# old_motorline.net
KiCad netlist of a schematic drawn in EAGLE
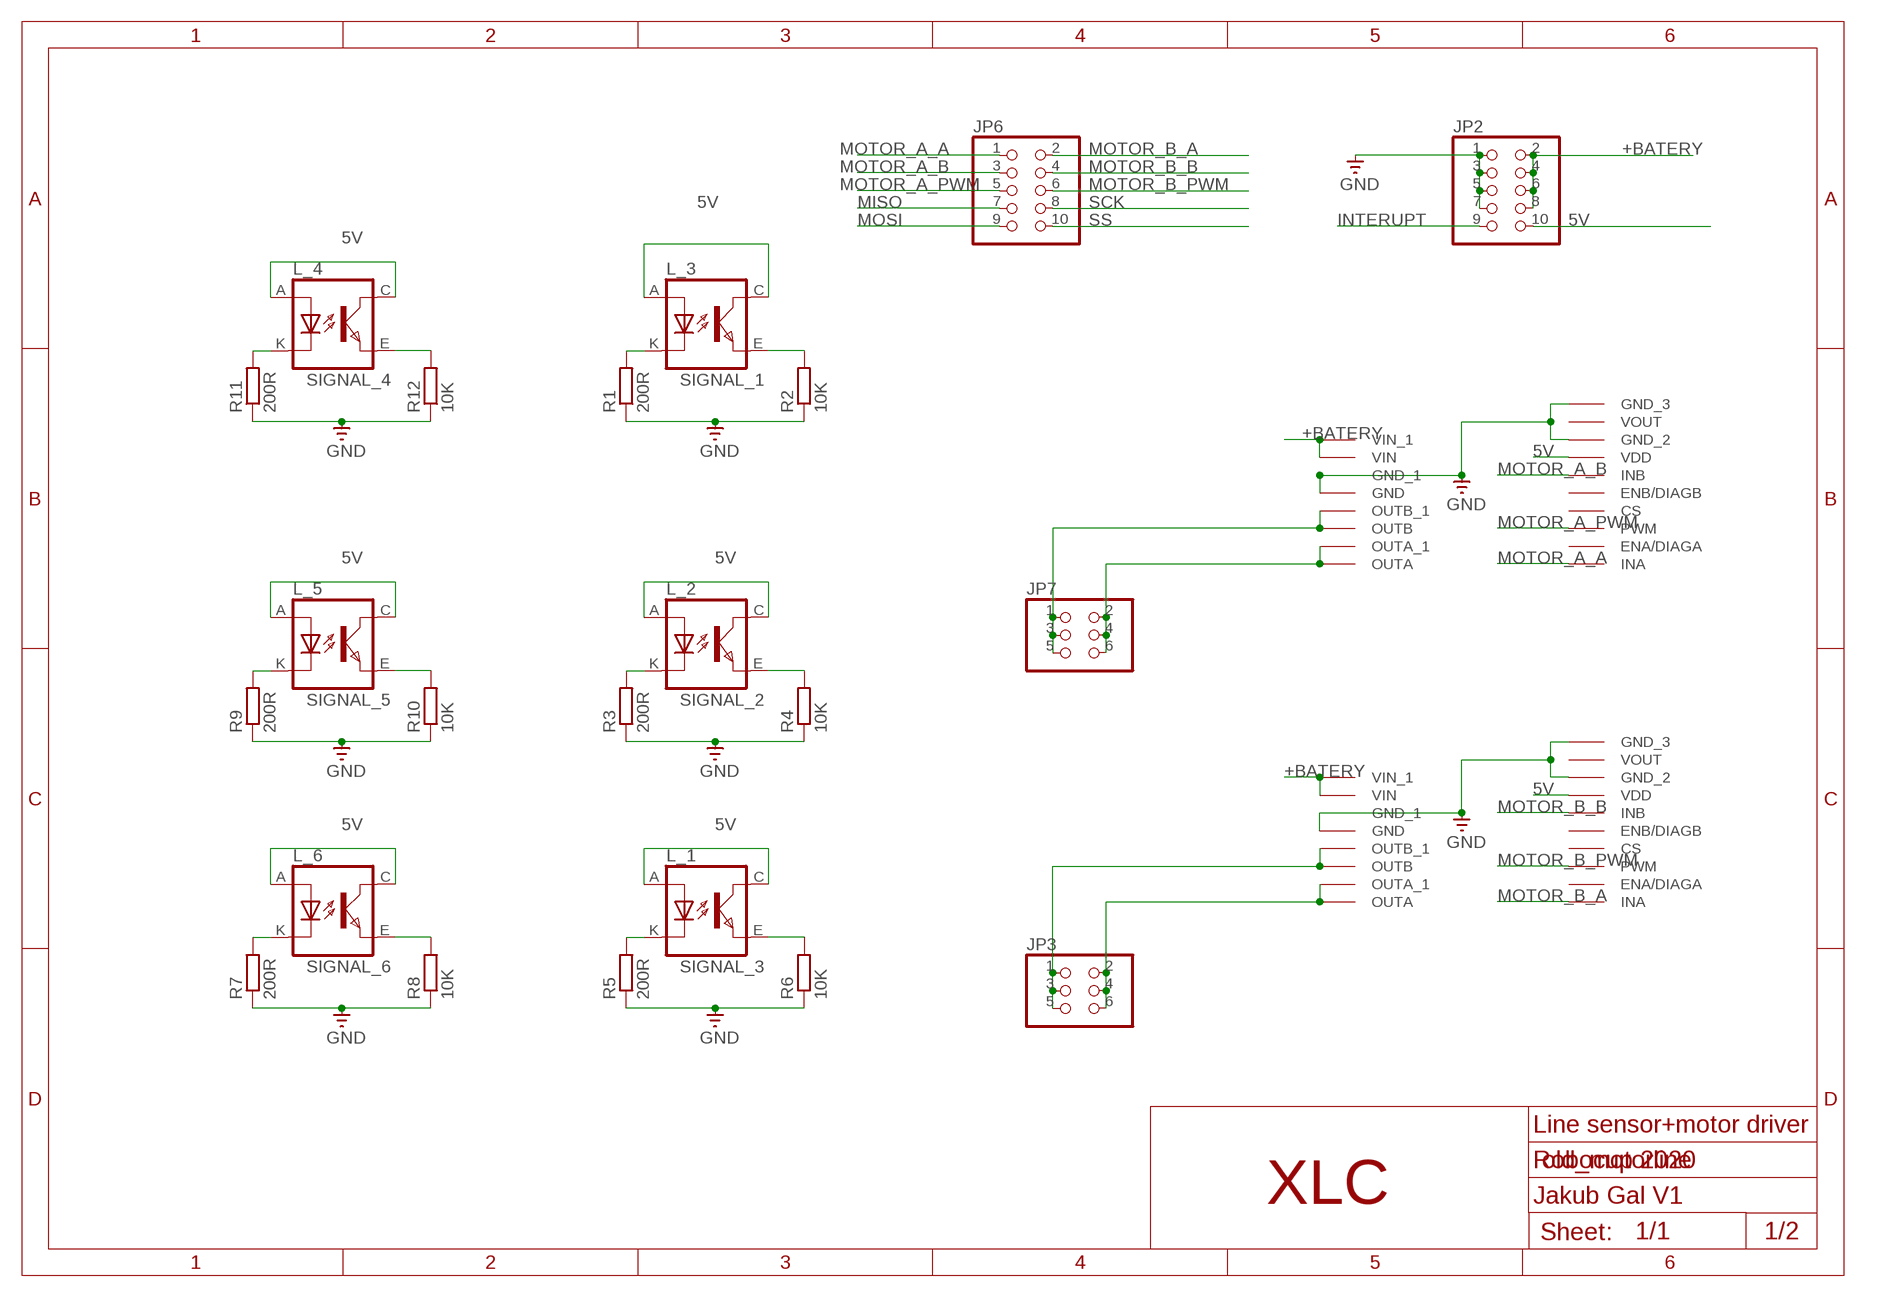
[diagram p0: schematic, sheet 1, part 1 of 2]
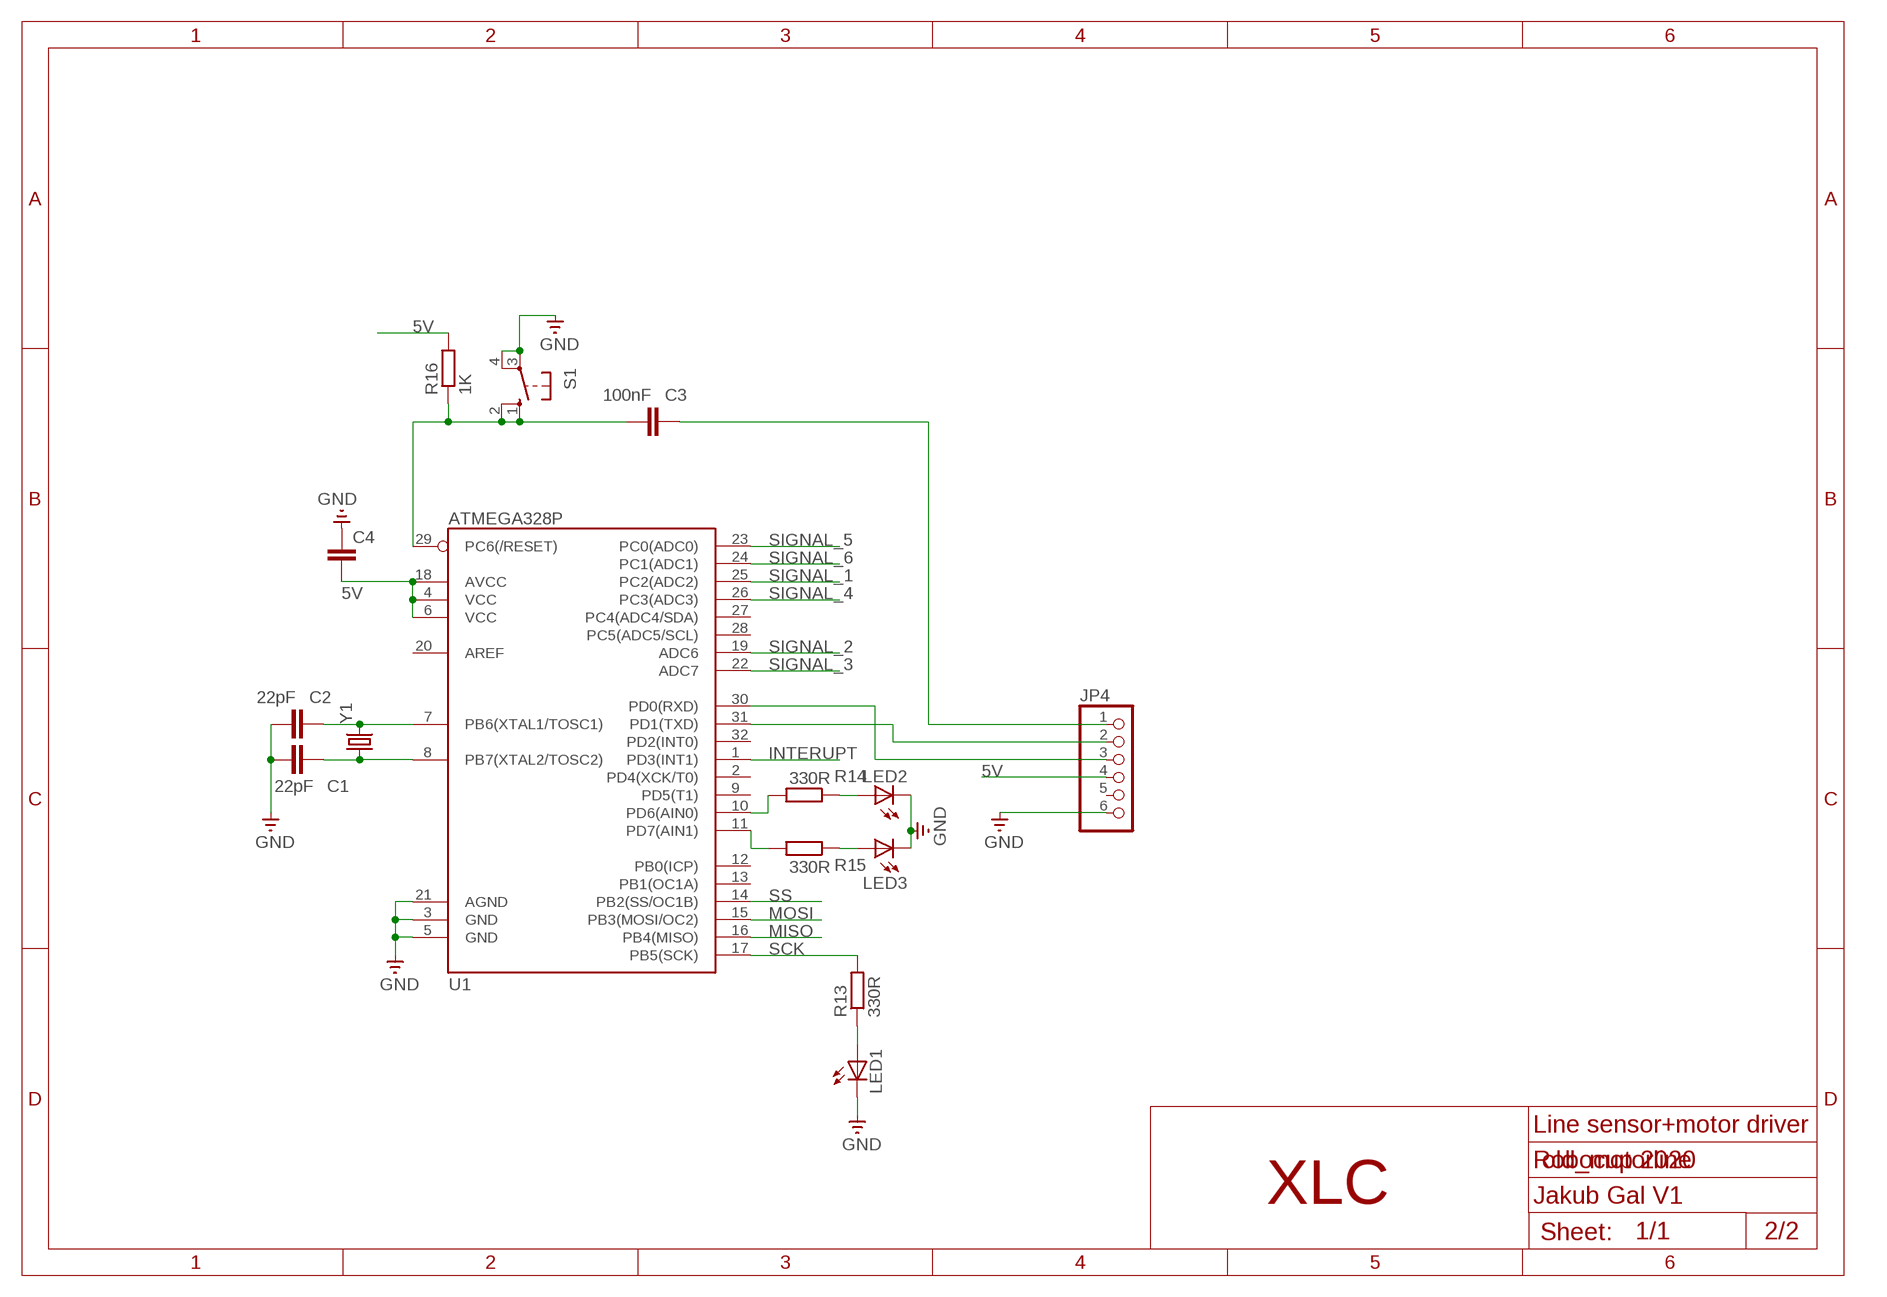
[diagram p1: schematic, sheet 1, part 2 of 2]

(export (version "E")
  (design (tool "Eeschema 10.0.6"))
  (components
    (comp (ref "C1")
      (value "22pF")
      (footprint "eagle-import:C0603")
      (libsource (lib "eagle-import") (part "rcl@1_C-EUC0603"))
    )
    (comp (ref "C2")
      (value "22pF")
      (footprint "eagle-import:C0603")
      (libsource (lib "eagle-import") (part "rcl@1_C-EUC0603"))
    )
    (comp (ref "C3")
      (value "100nF")
      (footprint "eagle-import:C0603")
      (libsource (lib "eagle-import") (part "rcl@1_C-EUC0603"))
    )
    (comp (ref "C4")
      (value "C-EUC0603")
      (footprint "eagle-import:C0603")
      (libsource (lib "eagle-import") (part "C-EUC0603"))
    )
    (comp (ref "JP2")
      (value "PINHD-2X5IDC")
      (footprint "eagle-import:2X05_IDC")
      (libsource (lib "eagle-import") (part "PINHD-2X5IDC"))
    )
    (comp (ref "JP3")
      (value "PINHD-2X3IDC")
      (footprint "eagle-import:2X03_IDC")
      (libsource (lib "eagle-import") (part "PINHD-2X3IDC"))
    )
    (comp (ref "JP4")
      (value "PINHD-1X6_2.54-90°")
      (footprint "eagle-import:1X06_90")
      (libsource (lib "eagle-import") (part "PINHD-1X6_2.54-90°"))
    )
    (comp (ref "JP6")
      (value "PINHD-2X5IDC")
      (footprint "eagle-import:2X05_IDC")
      (libsource (lib "eagle-import") (part "PINHD-2X5IDC"))
    )
    (comp (ref "JP7")
      (value "PINHD-2X3IDC")
      (footprint "eagle-import:2X03_IDC")
      (libsource (lib "eagle-import") (part "PINHD-2X3IDC"))
    )
    (comp (ref "LED1")
      (value "LEDCHIPLED_0603")
      (footprint "eagle-import:CHIPLED_0603")
      (libsource (lib "eagle-import") (part "LEDCHIPLED_0603"))
    )
    (comp (ref "LED2")
      (value "LEDCHIPLED_0603")
      (footprint "eagle-import:CHIPLED_0603")
      (libsource (lib "eagle-import") (part "LEDCHIPLED_0603"))
    )
    (comp (ref "LED3")
      (value "LEDCHIPLED_0603")
      (footprint "eagle-import:CHIPLED_0603")
      (libsource (lib "eagle-import") (part "LEDCHIPLED_0603"))
    )
    (comp (ref "L_1")
      (value "TCRT5000")
      (footprint "eagle-import:TCRT5000")
      (libsource (lib "eagle-import") (part "TCRT5000"))
    )
    (comp (ref "L_2")
      (value "TCRT5000")
      (footprint "eagle-import:TCRT5000")
      (libsource (lib "eagle-import") (part "TCRT5000"))
    )
    (comp (ref "L_3")
      (value "TCRT5000")
      (footprint "eagle-import:TCRT5000")
      (libsource (lib "eagle-import") (part "TCRT5000"))
    )
    (comp (ref "L_4")
      (value "TCRT5000")
      (footprint "eagle-import:TCRT5000")
      (fields (field (name "SPICEPREFIX") "O"))
      (libsource (lib "eagle-import") (part "TCRT5000"))
    )
    (comp (ref "L_5")
      (value "TCRT5000")
      (footprint "eagle-import:TCRT5000")
      (libsource (lib "eagle-import") (part "TCRT5000"))
    )
    (comp (ref "L_6")
      (value "TCRT5000")
      (footprint "eagle-import:TCRT5000")
      (fields (field (name "SPICEPREFIX") "O"))
      (libsource (lib "eagle-import") (part "TCRT5000"))
    )
    (comp (ref "R1")
      (value "200R")
      (footprint "eagle-import:R0603")
      (libsource (lib "eagle-import") (part "R-EU_R0603"))
    )
    (comp (ref "R2")
      (value "10K")
      (footprint "eagle-import:R0603")
      (libsource (lib "eagle-import") (part "R-EU_R0603"))
    )
    (comp (ref "R3")
      (value "200R")
      (footprint "eagle-import:R0603")
      (libsource (lib "eagle-import") (part "R-EU_R0603"))
    )
    (comp (ref "R4")
      (value "10K")
      (footprint "eagle-import:R0603")
      (libsource (lib "eagle-import") (part "R-EU_R0603"))
    )
    (comp (ref "R5")
      (value "200R")
      (footprint "eagle-import:R0603")
      (libsource (lib "eagle-import") (part "R-EU_R0603"))
    )
    (comp (ref "R6")
      (value "10K")
      (footprint "eagle-import:R0603")
      (libsource (lib "eagle-import") (part "R-EU_R0603"))
    )
    (comp (ref "R7")
      (value "200R")
      (footprint "eagle-import:R0603")
      (libsource (lib "eagle-import") (part "R-EU_R0603"))
    )
    (comp (ref "R8")
      (value "10K")
      (footprint "eagle-import:R0603")
      (libsource (lib "eagle-import") (part "R-EU_R0603"))
    )
    (comp (ref "R9")
      (value "200R")
      (footprint "eagle-import:R0603")
      (libsource (lib "eagle-import") (part "R-EU_R0603"))
    )
    (comp (ref "R10")
      (value "10K")
      (footprint "eagle-import:R0603")
      (libsource (lib "eagle-import") (part "R-EU_R0603"))
    )
    (comp (ref "R11")
      (value "200R")
      (footprint "eagle-import:R0603")
      (libsource (lib "eagle-import") (part "R-EU_R0603"))
    )
    (comp (ref "R12")
      (value "10K")
      (footprint "eagle-import:R0603")
      (libsource (lib "eagle-import") (part "R-EU_R0603"))
    )
    (comp (ref "R13")
      (value "330R")
      (footprint "eagle-import:R0603")
      (libsource (lib "eagle-import") (part "R-EU_R0603"))
    )
    (comp (ref "R14")
      (value "330R")
      (footprint "eagle-import:R0603")
      (libsource (lib "eagle-import") (part "R-EU_R0603"))
    )
    (comp (ref "R15")
      (value "330R")
      (footprint "eagle-import:R0603")
      (libsource (lib "eagle-import") (part "R-EU_R0603"))
    )
    (comp (ref "R16")
      (value "1K")
      (footprint "eagle-import:R0603")
      (libsource (lib "eagle-import") (part "R-EU_R0603"))
    )
    (comp (ref "S1")
      (value "10-XX")
      (footprint "eagle-import:B3F-10XX")
      (fields (field (name "MPN") "B3F-1000"))
      (libsource (lib "eagle-import") (part "10-XX"))
    )
    (comp (ref "U$1")
      (value "MOTOR_DRIVER")
      (footprint "eagle-import:MOTOR_DRIVER")
      (libsource (lib "eagle-import") (part "MOTOR_DRIVER"))
    )
    (comp (ref "U$2")
      (value "MOTOR_DRIVER")
      (footprint "eagle-import:MOTOR_DRIVER")
      (libsource (lib "eagle-import") (part "MOTOR_DRIVER"))
    )
    (comp (ref "U1")
      (value "ATMEGA328P")
      (footprint "eagle-import:TQFP32-08")
      (libsource (lib "eagle-import") (part "ATMEGA328_SMT"))
    )
    (comp (ref "Y1")
      (value "CRYSTALHC49US")
      (footprint "eagle-import:HC49US")
      (libsource (lib "eagle-import") (part "CRYSTALHC49US"))
    )
  )
  (nets
    (net (code "1") (name "/+BATERY") (class "Default")
      (node (ref "JP2") (pin "2") (pinfunction "2_2") (pintype "passive"))
      (node (ref "JP2") (pin "4") (pinfunction "4_4") (pintype "passive"))
      (node (ref "JP2") (pin "6") (pinfunction "6_6") (pintype "passive"))
      (node (ref "JP2") (pin "8") (pinfunction "8_8") (pintype "passive"))
      (node (ref "U$1") (pin "VIN") (pinfunction "VIN_VIN") (pintype "bidirectional"))
      (node (ref "U$1") (pin "VIN_1") (pinfunction "VIN_1_VIN_1") (pintype "bidirectional"))
      (node (ref "U$2") (pin "VIN") (pinfunction "VIN_VIN") (pintype "bidirectional"))
      (node (ref "U$2") (pin "VIN_1") (pinfunction "VIN_1_VIN_1") (pintype "bidirectional"))
    )
    (net (code "2") (name "/5V") (class "Default")
      (node (ref "C4") (pin "2") (pinfunction "2_2") (pintype "passive"))
      (node (ref "JP2") (pin "10") (pinfunction "10_10") (pintype "passive"))
      (node (ref "JP4") (pin "4") (pinfunction "4_4") (pintype "passive"))
      (node (ref "L_1") (pin "A") (pinfunction "ANODE_A") (pintype "passive"))
      (node (ref "L_1") (pin "C") (pinfunction "COLLECTOR_C") (pintype "passive"))
      (node (ref "L_2") (pin "A") (pinfunction "ANODE_A") (pintype "passive"))
      (node (ref "L_2") (pin "C") (pinfunction "COLLECTOR_C") (pintype "passive"))
      (node (ref "L_3") (pin "A") (pinfunction "ANODE_A") (pintype "passive"))
      (node (ref "L_3") (pin "C") (pinfunction "COLLECTOR_C") (pintype "passive"))
      (node (ref "L_4") (pin "A") (pinfunction "ANODE_A") (pintype "passive"))
      (node (ref "L_4") (pin "C") (pinfunction "COLLECTOR_C") (pintype "passive"))
      (node (ref "L_5") (pin "A") (pinfunction "ANODE_A") (pintype "passive"))
      (node (ref "L_5") (pin "C") (pinfunction "COLLECTOR_C") (pintype "passive"))
      (node (ref "L_6") (pin "A") (pinfunction "ANODE_A") (pintype "passive"))
      (node (ref "L_6") (pin "C") (pinfunction "COLLECTOR_C") (pintype "passive"))
      (node (ref "R16") (pin "2") (pinfunction "2_2") (pintype "passive"))
      (node (ref "U$1") (pin "VDD") (pinfunction "VDD_VDD") (pintype "bidirectional"))
      (node (ref "U$2") (pin "VDD") (pinfunction "VDD_VDD") (pintype "bidirectional"))
      (node (ref "U1") (pin "18") (pinfunction "AVCC_18") (pintype "bidirectional"))
      (node (ref "U1") (pin "4") (pinfunction "VCC_4") (pintype "bidirectional"))
      (node (ref "U1") (pin "6") (pinfunction "VCC_6") (pintype "bidirectional"))
    )
    (net (code "3") (name "/INTERUPT") (class "Default")
      (node (ref "JP2") (pin "9") (pinfunction "9_9") (pintype "passive"))
      (node (ref "U1") (pin "1") (pinfunction "PD3(INT1)_1") (pintype "bidirectional"))
    )
    (net (code "4") (name "/MISO") (class "Default")
      (node (ref "JP6") (pin "7") (pinfunction "7_7") (pintype "passive"))
      (node (ref "U1") (pin "16") (pinfunction "PB4(MISO)_16") (pintype "bidirectional"))
    )
    (net (code "5") (name "/MOSI") (class "Default")
      (node (ref "JP6") (pin "9") (pinfunction "9_9") (pintype "passive"))
      (node (ref "U1") (pin "15") (pinfunction "PB3(MOSI/OC2)_15") (pintype "bidirectional"))
    )
    (net (code "6") (name "/MOTOR_A_A") (class "Default")
      (node (ref "JP6") (pin "1") (pinfunction "1_1") (pintype "passive"))
      (node (ref "U$1") (pin "INA") (pinfunction "INA_INA") (pintype "bidirectional"))
    )
    (net (code "7") (name "/MOTOR_A_B") (class "Default")
      (node (ref "JP6") (pin "3") (pinfunction "3_3") (pintype "passive"))
      (node (ref "U$1") (pin "INB") (pinfunction "INB_INB") (pintype "bidirectional"))
    )
    (net (code "8") (name "/MOTOR_A_PWM") (class "Default")
      (node (ref "JP6") (pin "5") (pinfunction "5_5") (pintype "passive"))
      (node (ref "U$1") (pin "PWM") (pinfunction "PWM_PWM") (pintype "bidirectional"))
    )
    (net (code "9") (name "/MOTOR_B_A") (class "Default")
      (node (ref "JP6") (pin "2") (pinfunction "2_2") (pintype "passive"))
      (node (ref "U$2") (pin "INA") (pinfunction "INA_INA") (pintype "bidirectional"))
    )
    (net (code "10") (name "/MOTOR_B_B") (class "Default")
      (node (ref "JP6") (pin "4") (pinfunction "4_4") (pintype "passive"))
      (node (ref "U$2") (pin "INB") (pinfunction "INB_INB") (pintype "bidirectional"))
    )
    (net (code "11") (name "/MOTOR_B_PWM") (class "Default")
      (node (ref "JP6") (pin "6") (pinfunction "6_6") (pintype "passive"))
      (node (ref "U$2") (pin "PWM") (pinfunction "PWM_PWM") (pintype "bidirectional"))
    )
    (net (code "12") (name "/SCK") (class "Default")
      (node (ref "JP6") (pin "8") (pinfunction "8_8") (pintype "passive"))
      (node (ref "R13") (pin "2") (pinfunction "2_2") (pintype "passive"))
      (node (ref "U1") (pin "17") (pinfunction "PB5(SCK)_17") (pintype "bidirectional"))
    )
    (net (code "13") (name "/SIGNAL_1") (class "Default")
      (node (ref "L_3") (pin "E") (pinfunction "EMITTER_E") (pintype "passive"))
      (node (ref "R2") (pin "2") (pinfunction "2_2") (pintype "passive"))
      (node (ref "U1") (pin "25") (pinfunction "PC2(ADC2)_25") (pintype "bidirectional"))
    )
    (net (code "14") (name "/SIGNAL_2") (class "Default")
      (node (ref "L_2") (pin "E") (pinfunction "EMITTER_E") (pintype "passive"))
      (node (ref "R4") (pin "2") (pinfunction "2_2") (pintype "passive"))
      (node (ref "U1") (pin "19") (pinfunction "ADC6_19") (pintype "bidirectional"))
    )
    (net (code "15") (name "/SIGNAL_3") (class "Default")
      (node (ref "L_1") (pin "E") (pinfunction "EMITTER_E") (pintype "passive"))
      (node (ref "R6") (pin "2") (pinfunction "2_2") (pintype "passive"))
      (node (ref "U1") (pin "22") (pinfunction "ADC7_22") (pintype "bidirectional"))
    )
    (net (code "16") (name "/SIGNAL_4") (class "Default")
      (node (ref "L_4") (pin "E") (pinfunction "EMITTER_E") (pintype "passive"))
      (node (ref "R12") (pin "2") (pinfunction "2_2") (pintype "passive"))
      (node (ref "U1") (pin "26") (pinfunction "PC3(ADC3)_26") (pintype "bidirectional"))
    )
    (net (code "17") (name "/SIGNAL_5") (class "Default")
      (node (ref "L_5") (pin "E") (pinfunction "EMITTER_E") (pintype "passive"))
      (node (ref "R10") (pin "2") (pinfunction "2_2") (pintype "passive"))
      (node (ref "U1") (pin "23") (pinfunction "PC0(ADC0)_23") (pintype "bidirectional"))
    )
    (net (code "18") (name "/SIGNAL_6") (class "Default")
      (node (ref "L_6") (pin "E") (pinfunction "EMITTER_E") (pintype "passive"))
      (node (ref "R8") (pin "2") (pinfunction "2_2") (pintype "passive"))
      (node (ref "U1") (pin "24") (pinfunction "PC1(ADC1)_24") (pintype "bidirectional"))
    )
    (net (code "19") (name "/SS") (class "Default")
      (node (ref "JP6") (pin "10") (pinfunction "10_10") (pintype "passive"))
      (node (ref "U1") (pin "14") (pinfunction "PB2(SS/OC1B)_14") (pintype "bidirectional"))
    )
    (net (code "20") (name "GND") (class "Default")
      (node (ref "C1") (pin "1") (pinfunction "1_1") (pintype "passive"))
      (node (ref "C2") (pin "1") (pinfunction "1_1") (pintype "passive"))
      (node (ref "C4") (pin "1") (pinfunction "1_1") (pintype "passive"))
      (node (ref "JP2") (pin "1") (pinfunction "1_1") (pintype "passive"))
      (node (ref "JP2") (pin "3") (pinfunction "3_3") (pintype "passive"))
      (node (ref "JP2") (pin "5") (pinfunction "5_5") (pintype "passive"))
      (node (ref "JP2") (pin "7") (pinfunction "7_7") (pintype "passive"))
      (node (ref "JP4") (pin "6") (pinfunction "6_6") (pintype "passive"))
      (node (ref "LED1") (pin "C") (pinfunction "C_C") (pintype "passive"))
      (node (ref "LED2") (pin "C") (pinfunction "C_C") (pintype "passive"))
      (node (ref "LED3") (pin "C") (pinfunction "C_C") (pintype "passive"))
      (node (ref "R1") (pin "1") (pinfunction "1_1") (pintype "passive"))
      (node (ref "R10") (pin "1") (pinfunction "1_1") (pintype "passive"))
      (node (ref "R11") (pin "1") (pinfunction "1_1") (pintype "passive"))
      (node (ref "R12") (pin "1") (pinfunction "1_1") (pintype "passive"))
      (node (ref "R2") (pin "1") (pinfunction "1_1") (pintype "passive"))
      (node (ref "R3") (pin "1") (pinfunction "1_1") (pintype "passive"))
      (node (ref "R4") (pin "1") (pinfunction "1_1") (pintype "passive"))
      (node (ref "R5") (pin "1") (pinfunction "1_1") (pintype "passive"))
      (node (ref "R6") (pin "1") (pinfunction "1_1") (pintype "passive"))
      (node (ref "R7") (pin "1") (pinfunction "1_1") (pintype "passive"))
      (node (ref "R8") (pin "1") (pinfunction "1_1") (pintype "passive"))
      (node (ref "R9") (pin "1") (pinfunction "1_1") (pintype "passive"))
      (node (ref "S1") (pin "3") (pinfunction "P_3") (pintype "passive"))
      (node (ref "S1") (pin "4") (pinfunction "P1_4") (pintype "passive"))
      (node (ref "U$1") (pin "GND") (pinfunction "GND_GND") (pintype "bidirectional"))
      (node (ref "U$1") (pin "GND_1") (pinfunction "GND_1_GND_1") (pintype "bidirectional"))
      (node (ref "U$1") (pin "GND_2") (pinfunction "GND_2_GND_2") (pintype "bidirectional"))
      (node (ref "U$1") (pin "GND_3") (pinfunction "GND_3_GND_3") (pintype "bidirectional"))
      (node (ref "U$2") (pin "GND") (pinfunction "GND_GND") (pintype "bidirectional"))
      (node (ref "U$2") (pin "GND_1") (pinfunction "GND_1_GND_1") (pintype "bidirectional"))
      (node (ref "U$2") (pin "GND_2") (pinfunction "GND_2_GND_2") (pintype "bidirectional"))
      (node (ref "U$2") (pin "GND_3") (pinfunction "GND_3_GND_3") (pintype "bidirectional"))
      (node (ref "U1") (pin "21") (pinfunction "AGND_21") (pintype "bidirectional"))
      (node (ref "U1") (pin "3") (pinfunction "GND_3") (pintype "bidirectional"))
      (node (ref "U1") (pin "5") (pinfunction "GND_5") (pintype "bidirectional"))
    )
    (net (code "21") (name "Net-(C3-Pad2)") (class "Default")
      (node (ref "C3") (pin "2") (pinfunction "2_2") (pintype "passive"))
      (node (ref "JP4") (pin "1") (pinfunction "1_1") (pintype "passive"))
    )
    (net (code "22") (name "Net-(JP3-Pad1)") (class "Default")
      (node (ref "JP3") (pin "1") (pinfunction "1_1") (pintype "passive"))
      (node (ref "JP3") (pin "3") (pinfunction "3_3") (pintype "passive"))
      (node (ref "JP3") (pin "5") (pinfunction "5_5") (pintype "passive"))
      (node (ref "U$2") (pin "OUTB") (pinfunction "OUTB_OUTB") (pintype "bidirectional"))
      (node (ref "U$2") (pin "OUTB_1") (pinfunction "OUTB_1_OUTB_1") (pintype "bidirectional"))
    )
    (net (code "23") (name "Net-(JP3-Pad2)") (class "Default")
      (node (ref "JP3") (pin "2") (pinfunction "2_2") (pintype "passive"))
      (node (ref "JP3") (pin "4") (pinfunction "4_4") (pintype "passive"))
      (node (ref "JP3") (pin "6") (pinfunction "6_6") (pintype "passive"))
      (node (ref "U$2") (pin "OUTA") (pinfunction "OUTA_OUTA") (pintype "bidirectional"))
      (node (ref "U$2") (pin "OUTA_1") (pinfunction "OUTA_1_OUTA_1") (pintype "bidirectional"))
    )
    (net (code "24") (name "Net-(JP7-Pad1)") (class "Default")
      (node (ref "JP7") (pin "1") (pinfunction "1_1") (pintype "passive"))
      (node (ref "JP7") (pin "3") (pinfunction "3_3") (pintype "passive"))
      (node (ref "JP7") (pin "5") (pinfunction "5_5") (pintype "passive"))
      (node (ref "U$1") (pin "OUTB") (pinfunction "OUTB_OUTB") (pintype "bidirectional"))
      (node (ref "U$1") (pin "OUTB_1") (pinfunction "OUTB_1_OUTB_1") (pintype "bidirectional"))
    )
    (net (code "25") (name "Net-(JP7-Pad2)") (class "Default")
      (node (ref "JP7") (pin "2") (pinfunction "2_2") (pintype "passive"))
      (node (ref "JP7") (pin "4") (pinfunction "4_4") (pintype "passive"))
      (node (ref "JP7") (pin "6") (pinfunction "6_6") (pintype "passive"))
      (node (ref "U$1") (pin "OUTA") (pinfunction "OUTA_OUTA") (pintype "bidirectional"))
      (node (ref "U$1") (pin "OUTA_1") (pinfunction "OUTA_1_OUTA_1") (pintype "bidirectional"))
    )
    (net (code "26") (name "Net-(LED1-PadA)") (class "Default")
      (node (ref "LED1") (pin "A") (pinfunction "A_A") (pintype "passive"))
      (node (ref "R13") (pin "1") (pinfunction "1_1") (pintype "passive"))
    )
    (net (code "27") (name "Net-(LED2-PadA)") (class "Default")
      (node (ref "LED2") (pin "A") (pinfunction "A_A") (pintype "passive"))
      (node (ref "R14") (pin "1") (pinfunction "1_1") (pintype "passive"))
    )
    (net (code "28") (name "Net-(LED3-PadA)") (class "Default")
      (node (ref "LED3") (pin "A") (pinfunction "A_A") (pintype "passive"))
      (node (ref "R15") (pin "1") (pinfunction "1_1") (pintype "passive"))
    )
    (net (code "29") (name "Net-(L_1-CATHODE)") (class "Default")
      (node (ref "L_1") (pin "K") (pinfunction "CATHODE_K") (pintype "passive"))
      (node (ref "R5") (pin "2") (pinfunction "2_2") (pintype "passive"))
    )
    (net (code "30") (name "Net-(L_2-CATHODE)") (class "Default")
      (node (ref "L_2") (pin "K") (pinfunction "CATHODE_K") (pintype "passive"))
      (node (ref "R3") (pin "2") (pinfunction "2_2") (pintype "passive"))
    )
    (net (code "31") (name "Net-(L_3-CATHODE)") (class "Default")
      (node (ref "L_3") (pin "K") (pinfunction "CATHODE_K") (pintype "passive"))
      (node (ref "R1") (pin "2") (pinfunction "2_2") (pintype "passive"))
    )
    (net (code "32") (name "Net-(L_4-CATHODE)") (class "Default")
      (node (ref "L_4") (pin "K") (pinfunction "CATHODE_K") (pintype "passive"))
      (node (ref "R11") (pin "2") (pinfunction "2_2") (pintype "passive"))
    )
    (net (code "33") (name "Net-(L_5-CATHODE)") (class "Default")
      (node (ref "L_5") (pin "K") (pinfunction "CATHODE_K") (pintype "passive"))
      (node (ref "R9") (pin "2") (pinfunction "2_2") (pintype "passive"))
    )
    (net (code "34") (name "Net-(L_6-CATHODE)") (class "Default")
      (node (ref "L_6") (pin "K") (pinfunction "CATHODE_K") (pintype "passive"))
      (node (ref "R7") (pin "2") (pinfunction "2_2") (pintype "passive"))
    )
    (net (code "35") (name "Net-(S1-S)") (class "Default")
      (node (ref "C3") (pin "1") (pinfunction "1_1") (pintype "passive"))
      (node (ref "R16") (pin "1") (pinfunction "1_1") (pintype "passive"))
      (node (ref "S1") (pin "1") (pinfunction "S_1") (pintype "passive"))
      (node (ref "S1") (pin "2") (pinfunction "S1_2") (pintype "passive"))
      (node (ref "U1") (pin "29") (pinfunction "PC6(/RESET)_29") (pintype "bidirectional"))
    )
    (net (code "36") (name "Net-(U1-PB6(XTAL1{slash}TOSC1))") (class "Default")
      (node (ref "C2") (pin "2") (pinfunction "2_2") (pintype "passive"))
      (node (ref "U1") (pin "7") (pinfunction "PB6(XTAL1/TOSC1)_7") (pintype "bidirectional"))
      (node (ref "Y1") (pin "2") (pinfunction "2_2") (pintype "passive"))
    )
    (net (code "37") (name "Net-(U1-PB7(XTAL2{slash}TOSC2))") (class "Default")
      (node (ref "C1") (pin "2") (pinfunction "2_2") (pintype "passive"))
      (node (ref "U1") (pin "8") (pinfunction "PB7(XTAL2/TOSC2)_8") (pintype "bidirectional"))
      (node (ref "Y1") (pin "1") (pinfunction "1_1") (pintype "passive"))
    )
    (net (code "38") (name "Net-(U1-PD0(RXD))") (class "Default")
      (node (ref "JP4") (pin "3") (pinfunction "3_3") (pintype "passive"))
      (node (ref "U1") (pin "30") (pinfunction "PD0(RXD)_30") (pintype "bidirectional"))
    )
    (net (code "39") (name "Net-(U1-PD1(TXD))") (class "Default")
      (node (ref "JP4") (pin "2") (pinfunction "2_2") (pintype "passive"))
      (node (ref "U1") (pin "31") (pinfunction "PD1(TXD)_31") (pintype "bidirectional"))
    )
    (net (code "40") (name "Net-(U1-PD6(AIN0))") (class "Default")
      (node (ref "R14") (pin "2") (pinfunction "2_2") (pintype "passive"))
      (node (ref "U1") (pin "10") (pinfunction "PD6(AIN0)_10") (pintype "bidirectional"))
    )
    (net (code "41") (name "Net-(U1-PD7(AIN1))") (class "Default")
      (node (ref "R15") (pin "2") (pinfunction "2_2") (pintype "passive"))
      (node (ref "U1") (pin "11") (pinfunction "PD7(AIN1)_11") (pintype "bidirectional"))
    )
    (net (code "42") (name "unconnected-(JP4-Pad5)") (class "Default")
      (node (ref "JP4") (pin "5") (pinfunction "5_5") (pintype "passive"))
    )
    (net (code "43") (name "unconnected-(U$1-PadCS)") (class "Default")
      (node (ref "U$1") (pin "CS") (pinfunction "CS_CS") (pintype "bidirectional"))
    )
    (net (code "44") (name "unconnected-(U$1-PadENA{slash}DIAGA)") (class "Default")
      (node (ref "U$1") (pin "ENA/DIAGA") (pinfunction "ENA/DIAGA_ENA/DIAGA") (pintype "bidirectional"))
    )
    (net (code "45") (name "unconnected-(U$1-PadENB{slash}DIAGB)") (class "Default")
      (node (ref "U$1") (pin "ENB/DIAGB") (pinfunction "ENB/DIAGB_ENB/DIAGB") (pintype "bidirectional"))
    )
    (net (code "46") (name "unconnected-(U$1-PadVOUT)") (class "Default")
      (node (ref "U$1") (pin "VOUT") (pinfunction "VOUT_VOUT") (pintype "bidirectional"))
    )
    (net (code "47") (name "unconnected-(U$2-PadCS)") (class "Default")
      (node (ref "U$2") (pin "CS") (pinfunction "CS_CS") (pintype "bidirectional"))
    )
    (net (code "48") (name "unconnected-(U$2-PadENA{slash}DIAGA)") (class "Default")
      (node (ref "U$2") (pin "ENA/DIAGA") (pinfunction "ENA/DIAGA_ENA/DIAGA") (pintype "bidirectional"))
    )
    (net (code "49") (name "unconnected-(U$2-PadENB{slash}DIAGB)") (class "Default")
      (node (ref "U$2") (pin "ENB/DIAGB") (pinfunction "ENB/DIAGB_ENB/DIAGB") (pintype "bidirectional"))
    )
    (net (code "50") (name "unconnected-(U$2-PadVOUT)") (class "Default")
      (node (ref "U$2") (pin "VOUT") (pinfunction "VOUT_VOUT") (pintype "bidirectional"))
    )
    (net (code "51") (name "unconnected-(U1-AREF-Pad20)") (class "Default")
      (node (ref "U1") (pin "20") (pinfunction "AREF_20") (pintype "bidirectional"))
    )
    (net (code "52") (name "unconnected-(U1-PB0(ICP)-Pad12)") (class "Default")
      (node (ref "U1") (pin "12") (pinfunction "PB0(ICP)_12") (pintype "bidirectional"))
    )
    (net (code "53") (name "unconnected-(U1-PB1(OC1A)-Pad13)") (class "Default")
      (node (ref "U1") (pin "13") (pinfunction "PB1(OC1A)_13") (pintype "bidirectional"))
    )
    (net (code "54") (name "unconnected-(U1-PC4(ADC4{slash}SDA)-Pad27)") (class "Default")
      (node (ref "U1") (pin "27") (pinfunction "PC4(ADC4/SDA)_27") (pintype "bidirectional"))
    )
    (net (code "55") (name "unconnected-(U1-PC5(ADC5{slash}SCL)-Pad28)") (class "Default")
      (node (ref "U1") (pin "28") (pinfunction "PC5(ADC5/SCL)_28") (pintype "bidirectional"))
    )
    (net (code "56") (name "unconnected-(U1-PD2(INT0)-Pad32)") (class "Default")
      (node (ref "U1") (pin "32") (pinfunction "PD2(INT0)_32") (pintype "bidirectional"))
    )
    (net (code "57") (name "unconnected-(U1-PD4(XCK{slash}T0)-Pad2)") (class "Default")
      (node (ref "U1") (pin "2") (pinfunction "PD4(XCK/T0)_2") (pintype "bidirectional"))
    )
    (net (code "58") (name "unconnected-(U1-PD5(T1)-Pad9)") (class "Default")
      (node (ref "U1") (pin "9") (pinfunction "PD5(T1)_9") (pintype "bidirectional"))
    )
  )
)
